# External_Temp_Sensor.net
KiCad netlist of a schematic drawn in Altium Designer
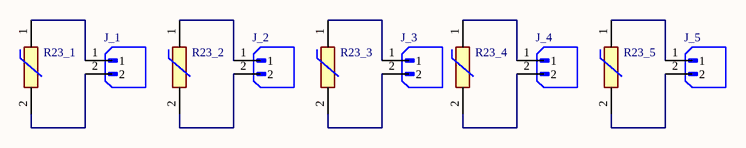
[diagram p0: External Temp Sensor.SchDoc]

(export (version "E")
  (design (tool "Eeschema 10.0.6"))
  (components
    (comp (ref "J_1")
      (value "B2B-XH-A(LF)(SN)")
      (footprint "JST_B2B-XH-A(LF)(SN)")
      (description "Connector Header Through Hole 2 position 0.098 (2.50mm)")
      (fields (field (name "MF") "JST Sales America Inc."))
      (libsource (lib "B2B-XH-A_LF__SN_") (part "B2B-XH-A(LF)(SN)"))
    )
    (comp (ref "J_2")
      (value "B2B-XH-A(LF)(SN)")
      (footprint "JST_B2B-XH-A(LF)(SN)")
      (description "Connector Header Through Hole 2 position 0.098 (2.50mm)")
      (fields (field (name "MF") "JST Sales America Inc."))
      (libsource (lib "B2B-XH-A_LF__SN_") (part "B2B-XH-A(LF)(SN)"))
    )
    (comp (ref "J_3")
      (value "B2B-XH-A(LF)(SN)")
      (footprint "JST_B2B-XH-A(LF)(SN)")
      (description "Connector Header Through Hole 2 position 0.098 (2.50mm)")
      (fields (field (name "MF") "JST Sales America Inc."))
      (libsource (lib "B2B-XH-A_LF__SN_") (part "B2B-XH-A(LF)(SN)"))
    )
    (comp (ref "J_4")
      (value "B2B-XH-A(LF)(SN)")
      (footprint "JST_B2B-XH-A(LF)(SN)")
      (description "Connector Header Through Hole 2 position 0.098 (2.50mm)")
      (fields (field (name "MF") "JST Sales America Inc."))
      (libsource (lib "B2B-XH-A_LF__SN_") (part "B2B-XH-A(LF)(SN)"))
    )
    (comp (ref "J_5")
      (value "B2B-XH-A(LF)(SN)")
      (footprint "JST_B2B-XH-A(LF)(SN)")
      (description "Connector Header Through Hole 2 position 0.098 (2.50mm)")
      (fields (field (name "MF") "JST Sales America Inc."))
      (libsource (lib "B2B-XH-A_LF__SN_") (part "B2B-XH-A(LF)(SN)"))
    )
    (comp (ref "R23_1")
      (value "NTCS0805E3104GMT")
      (footprint "SamacSys:THRMC2012X95N")
      (description "Thermistor")
      (fields (field (name "MOUSER PART NUMBER") "594-NTCS0805E3104GMT"))
      (libsource (lib "*") (part "NTCS0805E3104GMT"))
    )
    (comp (ref "R23_2")
      (value "NTCS0805E3104GMT")
      (footprint "SamacSys:THRMC2012X95N")
      (description "Thermistor")
      (fields (field (name "MOUSER PART NUMBER") "594-NTCS0805E3104GMT"))
      (libsource (lib "*") (part "NTCS0805E3104GMT"))
    )
    (comp (ref "R23_3")
      (value "NTCS0805E3104GMT")
      (footprint "SamacSys:THRMC2012X95N")
      (description "Thermistor")
      (fields (field (name "MOUSER PART NUMBER") "594-NTCS0805E3104GMT"))
      (libsource (lib "*") (part "NTCS0805E3104GMT"))
    )
    (comp (ref "R23_4")
      (value "NTCS0805E3104GMT")
      (footprint "SamacSys:THRMC2012X95N")
      (description "Thermistor")
      (fields (field (name "MOUSER PART NUMBER") "594-NTCS0805E3104GMT"))
      (libsource (lib "*") (part "NTCS0805E3104GMT"))
    )
    (comp (ref "R23_5")
      (value "NTCS0805E3104GMT")
      (footprint "SamacSys:THRMC2012X95N")
      (description "Thermistor")
      (fields (field (name "MOUSER PART NUMBER") "594-NTCS0805E3104GMT"))
      (libsource (lib "*") (part "NTCS0805E3104GMT"))
    )
  )
  (nets
    (net (code "1") (name "Net-(J_1-Pad1)") (class "Default")
      (node (ref "J_1") (pin "1") (pinfunction "1_1") (pintype "passive"))
      (node (ref "R23_1") (pin "1") (pinfunction "1_1") (pintype "passive"))
    )
    (net (code "2") (name "Net-(J_1-Pad2)") (class "Default")
      (node (ref "J_1") (pin "2") (pinfunction "2_2") (pintype "passive"))
      (node (ref "R23_1") (pin "2") (pinfunction "2_2") (pintype "passive"))
    )
    (net (code "3") (name "Net-(J_2-Pad1)") (class "Default")
      (node (ref "J_2") (pin "1") (pinfunction "1_1") (pintype "passive"))
      (node (ref "R23_2") (pin "1") (pinfunction "1_1") (pintype "passive"))
    )
    (net (code "4") (name "Net-(J_2-Pad2)") (class "Default")
      (node (ref "J_2") (pin "2") (pinfunction "2_2") (pintype "passive"))
      (node (ref "R23_2") (pin "2") (pinfunction "2_2") (pintype "passive"))
    )
    (net (code "5") (name "Net-(J_3-Pad1)") (class "Default")
      (node (ref "J_3") (pin "1") (pinfunction "1_1") (pintype "passive"))
      (node (ref "R23_3") (pin "1") (pinfunction "1_1") (pintype "passive"))
    )
    (net (code "6") (name "Net-(J_3-Pad2)") (class "Default")
      (node (ref "J_3") (pin "2") (pinfunction "2_2") (pintype "passive"))
      (node (ref "R23_3") (pin "2") (pinfunction "2_2") (pintype "passive"))
    )
    (net (code "7") (name "Net-(J_4-Pad1)") (class "Default")
      (node (ref "J_4") (pin "1") (pinfunction "1_1") (pintype "passive"))
      (node (ref "R23_4") (pin "1") (pinfunction "1_1") (pintype "passive"))
    )
    (net (code "8") (name "Net-(J_4-Pad2)") (class "Default")
      (node (ref "J_4") (pin "2") (pinfunction "2_2") (pintype "passive"))
      (node (ref "R23_4") (pin "2") (pinfunction "2_2") (pintype "passive"))
    )
    (net (code "9") (name "Net-(J_5-Pad1)") (class "Default")
      (node (ref "J_5") (pin "1") (pinfunction "1_1") (pintype "passive"))
      (node (ref "R23_5") (pin "1") (pinfunction "1_1") (pintype "passive"))
    )
    (net (code "10") (name "Net-(J_5-Pad2)") (class "Default")
      (node (ref "J_5") (pin "2") (pinfunction "2_2") (pintype "passive"))
      (node (ref "R23_5") (pin "2") (pinfunction "2_2") (pintype "passive"))
    )
  )
)
